# Modbus_RTU.net
KiCad netlist of a schematic drawn in Altium Designer
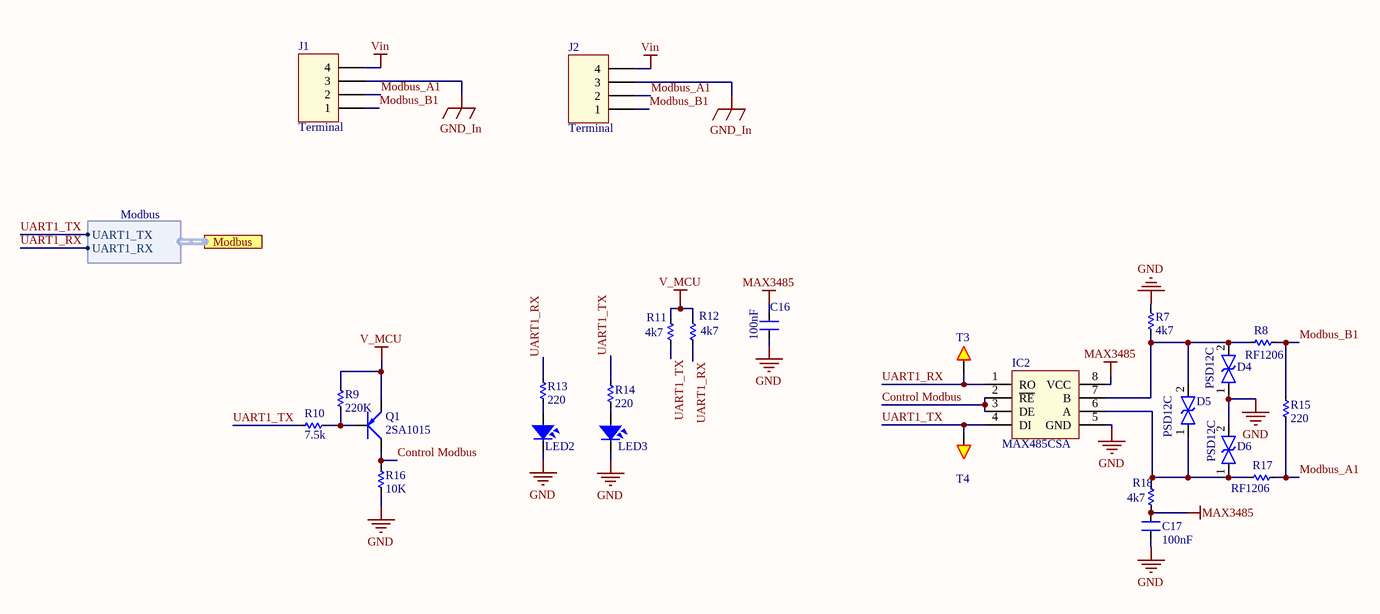
[diagram p0: Modbus RTU.SchDoc]

(export (version "E")
  (design (tool "Eeschema 10.0.6"))
  (components
    (comp (ref "C16") (value "100nF") (footprint "CN-SMD-0603") (libsource (lib "thu vien 3d") (part "CN")))
    (comp (ref "C17") (value "100nF") (footprint "CN-SMD-0603") (libsource (lib "thu vien 3d") (part "CN")))
    (comp (ref "D4")
      (value "PSD12C")
      (footprint "PSD12C")
      (description "diode tvs")
      (libsource (lib "Nichietsuvn") (part "PSD12C"))
    )
    (comp (ref "D5")
      (value "PSD12C")
      (footprint "PSD12C")
      (description "diode tvs")
      (libsource (lib "Nichietsuvn") (part "PSD12C"))
    )
    (comp (ref "D6")
      (value "PSD12C")
      (footprint "PSD12C")
      (description "diode tvs")
      (libsource (lib "Nichietsuvn") (part "PSD12C"))
    )
    (comp (ref "IC2")
      (value "MAX485CSA")
      (footprint "SO8")
      (description "RS232 - RS485 (Same sn75176)")
      (libsource (lib "thu vien 3d") (part "MAX485"))
    )
    (comp (ref "J1")
      (value "Terminal")
      (footprint "691305340004")
      (description "WR-TBL Serie 3053 - 3.81 mm Horizontal PCB Header with Plastic Latch, 04p")
      (fields (field (name "PART NUMBER") "691305340004") (field (name "PUBLISHER") "Wurth Elektronik"))
      (libsource (lib "header 3.81") (part "691305340004"))
    )
    (comp (ref "J2")
      (value "Terminal")
      (footprint "691305340004")
      (description "WR-TBL Serie 3053 - 3.81 mm Horizontal PCB Header with Plastic Latch, 04p")
      (fields (field (name "PART NUMBER") "691305340004") (field (name "PUBLISHER") "Wurth Elektronik"))
      (libsource (lib "header 3.81") (part "691305340004"))
    )
    (comp (ref "LED2")
      (value "LED")
      (footprint "LED-0805-Blue")
      (libsource (lib "thu vien 3d") (part "LED SMD"))
    )
    (comp (ref "LED3")
      (value "LED")
      (footprint "LED-0805-Blue")
      (libsource (lib "thu vien 3d") (part "LED SMD"))
    )
    (comp (ref "Q1")
      (value "2SA1015")
      (footprint "SOT23-321")
      (description "PNP 600mW, ECB")
      (libsource (lib "thu vien 3d") (part "2SA1015"))
    )
    (comp (ref "R7")
      (value "4k7")
      (footprint "RES-SMD-0603")
      (description "Resistor")
      (fields
        (field (name "MANUFACTURER") "Generic Components")
        (field (name "PUBLISHER") "Altium Hobart Technology Centre")
      )
      (libsource (lib "thu vien 3d") (part "Res-SMD"))
    )
    (comp (ref "R8")
      (value "RF1206")
      (footprint "RES-SMD-1206")
      (description "Resistor")
      (fields
        (field (name "MANUFACTURER") "Generic Components")
        (field (name "PUBLISHER") "Altium Hobart Technology Centre")
      )
      (libsource (lib "thu vien 3d") (part "Res-SMD"))
    )
    (comp (ref "R9")
      (value "220K")
      (footprint "RES-SMD-0603")
      (description "Resistor")
      (fields
        (field (name "MANUFACTURER") "Generic Components")
        (field (name "PUBLISHER") "Altium Hobart Technology Centre")
      )
      (libsource (lib "thu vien 3d") (part "Res-SMD"))
    )
    (comp (ref "R10")
      (value "7.5k")
      (footprint "RES-SMD-0603")
      (description "Resistor")
      (fields
        (field (name "MANUFACTURER") "Generic Components")
        (field (name "PUBLISHER") "Altium Hobart Technology Centre")
      )
      (libsource (lib "thu vien 3d") (part "Res-SMD"))
    )
    (comp (ref "R11")
      (value "4k7")
      (footprint "RES-SMD-0603")
      (description "Resistor")
      (fields
        (field (name "MANUFACTURER") "Generic Components")
        (field (name "PUBLISHER") "Altium Hobart Technology Centre")
      )
      (libsource (lib "thu vien 3d") (part "Res-SMD"))
    )
    (comp (ref "R12")
      (value "4k7")
      (footprint "RES-SMD-0603")
      (description "Resistor")
      (fields
        (field (name "MANUFACTURER") "Generic Components")
        (field (name "PUBLISHER") "Altium Hobart Technology Centre")
      )
      (libsource (lib "thu vien 3d") (part "Res-SMD"))
    )
    (comp (ref "R13")
      (value "220")
      (footprint "RES-SMD-0603")
      (description "Resistor")
      (fields
        (field (name "MANUFACTURER") "Generic Components")
        (field (name "PUBLISHER") "Altium Hobart Technology Centre")
      )
      (libsource (lib "thu vien 3d") (part "Res-SMD"))
    )
    (comp (ref "R14")
      (value "220")
      (footprint "RES-SMD-0603")
      (description "Resistor")
      (fields
        (field (name "MANUFACTURER") "Generic Components")
        (field (name "PUBLISHER") "Altium Hobart Technology Centre")
      )
      (libsource (lib "thu vien 3d") (part "Res-SMD"))
    )
    (comp (ref "R15")
      (value "220")
      (footprint "RES-SMD-0603")
      (description "Resistor")
      (fields
        (field (name "MANUFACTURER") "Generic Components")
        (field (name "PUBLISHER") "Altium Hobart Technology Centre")
      )
      (libsource (lib "thu vien 3d") (part "Res-SMD"))
    )
    (comp (ref "R16")
      (value "10K")
      (footprint "RES-SMD-0603")
      (description "Resistor")
      (fields
        (field (name "MANUFACTURER") "Generic Components")
        (field (name "PUBLISHER") "Altium Hobart Technology Centre")
      )
      (libsource (lib "thu vien 3d") (part "Res-SMD"))
    )
    (comp (ref "R17")
      (value "RF1206")
      (footprint "RES-SMD-1206")
      (description "Resistor")
      (fields
        (field (name "MANUFACTURER") "Generic Components")
        (field (name "PUBLISHER") "Altium Hobart Technology Centre")
      )
      (libsource (lib "thu vien 3d") (part "Res-SMD"))
    )
    (comp (ref "R18")
      (value "4k7")
      (footprint "RES-SMD-0603")
      (description "Resistor")
      (fields
        (field (name "MANUFACTURER") "Generic Components")
        (field (name "PUBLISHER") "Altium Hobart Technology Centre")
      )
      (libsource (lib "thu vien 3d") (part "Res-SMD"))
    )
    (comp (ref "T3")
      (value "Test")
      (footprint "Test")
      (description "WR-PHD 2.54 mm Angled Socket Header")
      (fields
        (field (name "MANUFACTURER") "Würth Elektronik eiSos GmbH")
        (field (name "PARTNO") "613002143121")
        (field (name "CREATED BY") "Karrer Zheng")
      )
      (libsource (lib "Nichietsuvn") (part "Test"))
    )
    (comp (ref "T4")
      (value "Test")
      (footprint "Test")
      (description "WR-PHD 2.54 mm Angled Socket Header")
      (fields
        (field (name "MANUFACTURER") "Würth Elektronik eiSos GmbH")
        (field (name "PARTNO") "613002143121")
        (field (name "CREATED BY") "Karrer Zheng")
      )
      (libsource (lib "Nichietsuvn") (part "Test"))
    )
  )
  (nets
    (net (code "2") (name "/Control Modbus") (class "Default")
      (node (ref "IC2") (pin "2") (pinfunction "~{RE}_2") (pintype "passive"))
      (node (ref "IC2") (pin "3") (pinfunction "DE_3") (pintype "passive"))
      (node (ref "Q1") (pin "2") (pinfunction "C_2") (pintype "passive"))
      (node (ref "R16") (pin "2") (pinfunction "2_2") (pintype "passive"))
    )
    (net (code "3") (name "/Modbus_A1") (class "Default")
      (node (ref "J1") (pin "2") (pinfunction "2_2") (pintype "passive"))
      (node (ref "J2") (pin "2") (pinfunction "2_2") (pintype "passive"))
      (node (ref "R15") (pin "2") (pinfunction "2_2") (pintype "passive"))
      (node (ref "R17") (pin "1") (pinfunction "1_1") (pintype "passive"))
    )
    (net (code "4") (name "/Modbus_B1") (class "Default")
      (node (ref "J1") (pin "1") (pinfunction "1_1") (pintype "passive"))
      (node (ref "J2") (pin "1") (pinfunction "1_1") (pintype "passive"))
      (node (ref "R15") (pin "1") (pinfunction "1_1") (pintype "passive"))
      (node (ref "R8") (pin "1") (pinfunction "1_1") (pintype "passive"))
    )
    (net (code "5") (name "/UART1_RX") (class "Default")
      (node (ref "IC2") (pin "1") (pinfunction "RO_1") (pintype "passive"))
      (node (ref "R12") (pin "2") (pinfunction "2_2") (pintype "passive"))
      (node (ref "R13") (pin "1") (pinfunction "1_1") (pintype "passive"))
      (node (ref "T3") (pin "1") (pinfunction "1_1") (pintype "passive"))
    )
    (net (code "6") (name "/UART1_TX") (class "Default")
      (node (ref "IC2") (pin "4") (pinfunction "DI_4") (pintype "passive"))
      (node (ref "R10") (pin "1") (pinfunction "1_1") (pintype "passive"))
      (node (ref "R11") (pin "2") (pinfunction "2_2") (pintype "passive"))
      (node (ref "R14") (pin "1") (pinfunction "1_1") (pintype "passive"))
      (node (ref "T4") (pin "1") (pinfunction "1_1") (pintype "passive"))
    )
    (net (code "8") (name "GND") (class "Default")
      (node (ref "C16") (pin "1") (pinfunction "1_1") (pintype "passive"))
      (node (ref "C17") (pin "2") (pinfunction "2_2") (pintype "passive"))
      (node (ref "D4") (pin "1") (pinfunction "1_1") (pintype "passive"))
      (node (ref "D6") (pin "2") (pinfunction "2_2") (pintype "passive"))
      (node (ref "IC2") (pin "5") (pinfunction "GND_5") (pintype "passive"))
      (node (ref "LED2") (pin "2") (pinfunction "2_2") (pintype "passive"))
      (node (ref "LED3") (pin "2") (pinfunction "2_2") (pintype "passive"))
      (node (ref "R16") (pin "1") (pinfunction "1_1") (pintype "passive"))
      (node (ref "R7") (pin "1") (pinfunction "1_1") (pintype "passive"))
    )
    (net (code "9") (name "GND_In") (class "Default")
      (node (ref "J1") (pin "3") (pinfunction "3_3") (pintype "passive"))
      (node (ref "J2") (pin "3") (pinfunction "3_3") (pintype "passive"))
    )
    (net (code "10") (name "MAX3485") (class "Default")
      (node (ref "C16") (pin "2") (pinfunction "2_2") (pintype "passive"))
      (node (ref "C17") (pin "1") (pinfunction "1_1") (pintype "passive"))
      (node (ref "IC2") (pin "8") (pinfunction "VCC_8") (pintype "passive"))
      (node (ref "R18") (pin "1") (pinfunction "1_1") (pintype "passive"))
    )
    (net (code "11") (name "Net-(IC2-A)") (class "Default")
      (node (ref "D5") (pin "1") (pinfunction "1_1") (pintype "passive"))
      (node (ref "D6") (pin "1") (pinfunction "1_1") (pintype "passive"))
      (node (ref "IC2") (pin "6") (pinfunction "A_6") (pintype "passive"))
      (node (ref "R17") (pin "2") (pinfunction "2_2") (pintype "passive"))
      (node (ref "R18") (pin "2") (pinfunction "2_2") (pintype "passive"))
    )
    (net (code "12") (name "Net-(IC2-B)") (class "Default")
      (node (ref "D4") (pin "2") (pinfunction "2_2") (pintype "passive"))
      (node (ref "D5") (pin "2") (pinfunction "2_2") (pintype "passive"))
      (node (ref "IC2") (pin "7") (pinfunction "B_7") (pintype "passive"))
      (node (ref "R7") (pin "2") (pinfunction "2_2") (pintype "passive"))
      (node (ref "R8") (pin "2") (pinfunction "2_2") (pintype "passive"))
    )
    (net (code "13") (name "Net-(LED2-Pad1)") (class "Default")
      (node (ref "LED2") (pin "1") (pinfunction "1_1") (pintype "passive"))
      (node (ref "R13") (pin "2") (pinfunction "2_2") (pintype "passive"))
    )
    (net (code "14") (name "Net-(LED3-Pad1)") (class "Default")
      (node (ref "LED3") (pin "1") (pinfunction "1_1") (pintype "passive"))
      (node (ref "R14") (pin "2") (pinfunction "2_2") (pintype "passive"))
    )
    (net (code "15") (name "Net-(Q1-B)") (class "Default")
      (node (ref "Q1") (pin "3") (pinfunction "B_3") (pintype "passive"))
      (node (ref "R10") (pin "2") (pinfunction "2_2") (pintype "passive"))
      (node (ref "R9") (pin "1") (pinfunction "1_1") (pintype "passive"))
    )
    (net (code "16") (name "V_MCU") (class "Default")
      (node (ref "Q1") (pin "1") (pinfunction "E_1") (pintype "passive"))
      (node (ref "R11") (pin "1") (pinfunction "1_1") (pintype "passive"))
      (node (ref "R12") (pin "1") (pinfunction "1_1") (pintype "passive"))
      (node (ref "R9") (pin "2") (pinfunction "2_2") (pintype "passive"))
    )
    (net (code "17") (name "Vin") (class "Default")
      (node (ref "J1") (pin "4") (pinfunction "4_4") (pintype "passive"))
      (node (ref "J2") (pin "4") (pinfunction "4_4") (pintype "passive"))
    )
  )
)
